# C1_Interface.net
KiCad netlist of a schematic drawn in EAGLE
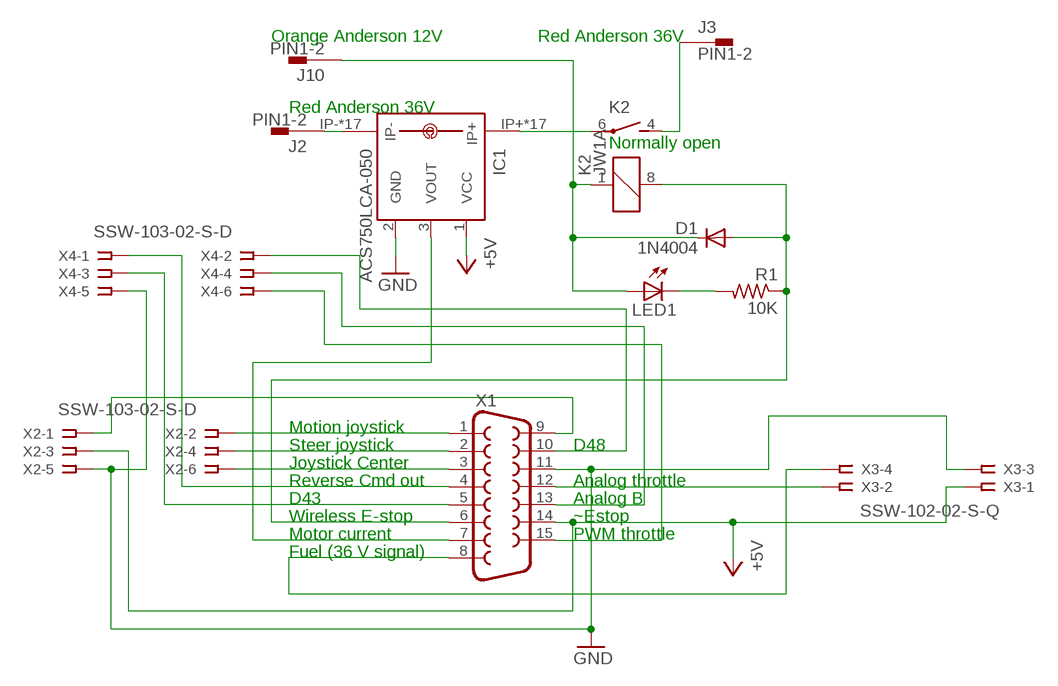
[diagram p0: schematic, sheet 1]

(export (version "E")
  (design (tool "Eeschema 10.0.6"))
  (components
    (comp (ref "D1")
      (value "1N4004")
      (footprint "eagle-import:DO41-10")
      (libsource (lib "eagle-import") (part "1N4004"))
    )
    (comp (ref "IC1")
      (value "ACS750LCA-050")
      (footprint "eagle-import:ACS75050")
      (fields (field (name "MF") "ALLEGRO MICROSYSTEMS, INC."))
      (libsource (lib "eagle-import") (part "ACS750CA-050L"))
    )
    (comp (ref "J2")
      (value "PIN1-2")
      (footprint "eagle-import:62221")
      (fields (field (name "MF") "TYCO ELECTRONICS") (field (name "MPN") "62221-1"))
      (libsource (lib "eagle-import") (part "PIN1-2"))
    )
    (comp (ref "J3")
      (value "PIN1-2")
      (footprint "eagle-import:62221")
      (fields (field (name "MF") "TYCO ELECTRONICS") (field (name "MPN") "62221-1"))
      (libsource (lib "eagle-import") (part "PIN1-2"))
    )
    (comp (ref "J10")
      (value "PIN1-2")
      (footprint "eagle-import:62221")
      (fields (field (name "MF") "TYCO ELECTRONICS") (field (name "MPN") "62221-1"))
      (libsource (lib "eagle-import") (part "PIN1-2"))
    )
    (comp (ref "K2")
      (value "JW1A")
      (footprint "eagle-import:JW1A")
      (libsource (lib "eagle-import") (part "JW1A"))
    )
    (comp (ref "LED1")
      (value "LED3MM")
      (footprint "eagle-import:LED3MM")
      (libsource (lib "eagle-import") (part "LED3MM"))
    )
    (comp (ref "R1")
      (value "10K")
      (footprint "eagle-import:0204_5")
      (libsource (lib "eagle-import") (part "R-US_0204/5"))
    )
    (comp (ref "X1")
      (value "F15H")
      (footprint "eagle-import:F15H")
      (libsource (lib "eagle-import") (part "F15H"))
    )
    (comp (ref "X2")
      (value "SSW-103-02-S-D")
      (footprint "eagle-import:SSW-103-02-S-D")
      (libsource (lib "eagle-import") (part "SSW-103-02-S-D"))
    )
    (comp (ref "X3")
      (value "SSW-102-02-S-Q")
      (footprint "eagle-import:SSW-102-02-S-Q")
      (libsource (lib "eagle-import") (part "SSW-102-02-S-Q"))
    )
    (comp (ref "X4")
      (value "SSW-103-02-S-D")
      (footprint "eagle-import:SSW-103-02-S-D")
      (libsource (lib "eagle-import") (part "SSW-103-02-S-D"))
    )
  )
  (nets
    (net (code "1") (name "+5V") (class "Default")
      (node (ref "IC1") (pin "1") (pinfunction "VCC_1") (pintype "power_in"))
      (node (ref "X1") (pin "14") (pinfunction "14_14") (pintype "passive"))
      (node (ref "X2") (pin "3") (pinfunction "1_3") (pintype "passive"))
      (node (ref "X3") (pin "1") (pinfunction "1_1") (pintype "passive"))
    )
    (net (code "2") (name "GND") (class "Default")
      (node (ref "IC1") (pin "2") (pinfunction "GND_2") (pintype "power_in"))
      (node (ref "X1") (pin "11") (pinfunction "11_11") (pintype "passive"))
      (node (ref "X2") (pin "5") (pinfunction "1_5") (pintype "passive"))
      (node (ref "X3") (pin "3") (pinfunction "1_3") (pintype "passive"))
      (node (ref "X4") (pin "5") (pinfunction "1_5") (pintype "passive"))
    )
    (net (code "3") (name "Net-(D1-PadC)") (class "Default")
      (node (ref "D1") (pin "C") (pinfunction "C_C") (pintype "passive"))
      (node (ref "J10") (pin "1") (pinfunction "1_1") (pintype "passive"))
      (node (ref "K2") (pin "1") (pinfunction "1_1") (pintype "passive"))
      (node (ref "LED1") (pin "A") (pinfunction "A_A") (pintype "passive"))
    )
    (net (code "4") (name "Net-(IC1-IP--PadIP-@10)") (class "Default")
      (node (ref "IC1") (pin "IP-") (pinfunction "IP-_IP-") (pintype "passive"))
      (node (ref "IC1") (pin "IP-@10") (pinfunction "IP-_IP-@10") (pintype "passive"))
      (node (ref "IC1") (pin "IP-@11") (pinfunction "IP-_IP-@11") (pintype "passive"))
      (node (ref "IC1") (pin "IP-@12") (pinfunction "IP-_IP-@12") (pintype "passive"))
      (node (ref "IC1") (pin "IP-@13") (pinfunction "IP-_IP-@13") (pintype "passive"))
      (node (ref "IC1") (pin "IP-@14") (pinfunction "IP-_IP-@14") (pintype "passive"))
      (node (ref "IC1") (pin "IP-@15") (pinfunction "IP-_IP-@15") (pintype "passive"))
      (node (ref "IC1") (pin "IP-@16") (pinfunction "IP-_IP-@16") (pintype "passive"))
      (node (ref "IC1") (pin "IP-@17") (pinfunction "IP-_IP-@17") (pintype "passive"))
      (node (ref "IC1") (pin "IP-@2") (pinfunction "IP-_IP-@2") (pintype "passive"))
      (node (ref "IC1") (pin "IP-@3") (pinfunction "IP-_IP-@3") (pintype "passive"))
      (node (ref "IC1") (pin "IP-@4") (pinfunction "IP-_IP-@4") (pintype "passive"))
      (node (ref "IC1") (pin "IP-@5") (pinfunction "IP-_IP-@5") (pintype "passive"))
      (node (ref "IC1") (pin "IP-@6") (pinfunction "IP-_IP-@6") (pintype "passive"))
      (node (ref "IC1") (pin "IP-@7") (pinfunction "IP-_IP-@7") (pintype "passive"))
      (node (ref "IC1") (pin "IP-@8") (pinfunction "IP-_IP-@8") (pintype "passive"))
      (node (ref "IC1") (pin "IP-@9") (pinfunction "IP-_IP-@9") (pintype "passive"))
      (node (ref "J2") (pin "1") (pinfunction "1_1") (pintype "passive"))
    )
    (net (code "5") (name "Net-(IC1-VOUT)") (class "Default")
      (node (ref "IC1") (pin "3") (pinfunction "VOUT_3") (pintype "output"))
      (node (ref "X1") (pin "7") (pinfunction "7_7") (pintype "passive"))
    )
    (net (code "6") (name "Net-(K2A-P)") (class "Default")
      (node (ref "IC1") (pin "IP+") (pinfunction "IP+_IP+") (pintype "passive"))
      (node (ref "IC1") (pin "IP+@10") (pinfunction "IP+_IP+@10") (pintype "passive"))
      (node (ref "IC1") (pin "IP+@11") (pinfunction "IP+_IP+@11") (pintype "passive"))
      (node (ref "IC1") (pin "IP+@12") (pinfunction "IP+_IP+@12") (pintype "passive"))
      (node (ref "IC1") (pin "IP+@13") (pinfunction "IP+_IP+@13") (pintype "passive"))
      (node (ref "IC1") (pin "IP+@14") (pinfunction "IP+_IP+@14") (pintype "passive"))
      (node (ref "IC1") (pin "IP+@15") (pinfunction "IP+_IP+@15") (pintype "passive"))
      (node (ref "IC1") (pin "IP+@16") (pinfunction "IP+_IP+@16") (pintype "passive"))
      (node (ref "IC1") (pin "IP+@17") (pinfunction "IP+_IP+@17") (pintype "passive"))
      (node (ref "IC1") (pin "IP+@2") (pinfunction "IP+_IP+@2") (pintype "passive"))
      (node (ref "IC1") (pin "IP+@3") (pinfunction "IP+_IP+@3") (pintype "passive"))
      (node (ref "IC1") (pin "IP+@4") (pinfunction "IP+_IP+@4") (pintype "passive"))
      (node (ref "IC1") (pin "IP+@5") (pinfunction "IP+_IP+@5") (pintype "passive"))
      (node (ref "IC1") (pin "IP+@6") (pinfunction "IP+_IP+@6") (pintype "passive"))
      (node (ref "IC1") (pin "IP+@7") (pinfunction "IP+_IP+@7") (pintype "passive"))
      (node (ref "IC1") (pin "IP+@8") (pinfunction "IP+_IP+@8") (pintype "passive"))
      (node (ref "IC1") (pin "IP+@9") (pinfunction "IP+_IP+@9") (pintype "passive"))
      (node (ref "K2") (pin "6") (pinfunction "P_6") (pintype "passive"))
    )
    (net (code "7") (name "Net-(K2A-S)") (class "Default")
      (node (ref "J3") (pin "1") (pinfunction "1_1") (pintype "passive"))
      (node (ref "K2") (pin "4") (pinfunction "S_4") (pintype "passive"))
    )
    (net (code "8") (name "Net-(K2B-2)") (class "Default")
      (node (ref "D1") (pin "A") (pinfunction "A_A") (pintype "passive"))
      (node (ref "K2") (pin "8") (pinfunction "2_8") (pintype "passive"))
      (node (ref "R1") (pin "1") (pinfunction "1_1") (pintype "passive"))
      (node (ref "X1") (pin "6") (pinfunction "6_6") (pintype "passive"))
    )
    (net (code "9") (name "Net-(LED1-C)") (class "Default")
      (node (ref "LED1") (pin "K") (pinfunction "C_K") (pintype "passive"))
      (node (ref "R1") (pin "2") (pinfunction "2_2") (pintype "passive"))
    )
    (net (code "10") (name "Net-(X1-Pad4)") (class "Default")
      (node (ref "X1") (pin "4") (pinfunction "4_4") (pintype "passive"))
      (node (ref "X4") (pin "1") (pinfunction "1_1") (pintype "passive"))
    )
    (net (code "11") (name "Net-(X1-Pad9)") (class "Default")
      (node (ref "X1") (pin "9") (pinfunction "9_9") (pintype "passive"))
      (node (ref "X2") (pin "1") (pinfunction "1_1") (pintype "passive"))
    )
    (net (code "12") (name "Net-(X2B-1)") (class "Default")
      (node (ref "X1") (pin "1") (pinfunction "1_1") (pintype "passive"))
      (node (ref "X2") (pin "2") (pinfunction "1_2") (pintype "passive"))
    )
    (net (code "13") (name "Net-(X2D-1)") (class "Default")
      (node (ref "X1") (pin "2") (pinfunction "2_2") (pintype "passive"))
      (node (ref "X2") (pin "4") (pinfunction "1_4") (pintype "passive"))
    )
    (net (code "14") (name "Net-(X2F-1)") (class "Default")
      (node (ref "X1") (pin "3") (pinfunction "3_3") (pintype "passive"))
      (node (ref "X2") (pin "6") (pinfunction "1_6") (pintype "passive"))
    )
    (net (code "15") (name "Net-(X3B-1)") (class "Default")
      (node (ref "X1") (pin "12") (pinfunction "12_12") (pintype "passive"))
      (node (ref "X3") (pin "2") (pinfunction "1_2") (pintype "passive"))
    )
    (net (code "16") (name "Net-(X3D-1)") (class "Default")
      (node (ref "X1") (pin "8") (pinfunction "8_8") (pintype "passive"))
      (node (ref "X3") (pin "4") (pinfunction "1_4") (pintype "passive"))
    )
    (net (code "17") (name "Net-(X4B-1)") (class "Default")
      (node (ref "X1") (pin "10") (pinfunction "10_10") (pintype "passive"))
      (node (ref "X4") (pin "2") (pinfunction "1_2") (pintype "passive"))
    )
    (net (code "18") (name "Net-(X4C-1)") (class "Default")
      (node (ref "X1") (pin "5") (pinfunction "5_5") (pintype "passive"))
      (node (ref "X4") (pin "3") (pinfunction "1_3") (pintype "passive"))
    )
    (net (code "19") (name "Net-(X4D-1)") (class "Default")
      (node (ref "X1") (pin "13") (pinfunction "13_13") (pintype "passive"))
      (node (ref "X4") (pin "4") (pinfunction "1_4") (pintype "passive"))
    )
    (net (code "20") (name "Net-(X4F-1)") (class "Default")
      (node (ref "X1") (pin "15") (pinfunction "15_15") (pintype "passive"))
      (node (ref "X4") (pin "6") (pinfunction "1_6") (pintype "passive"))
    )
  )
)
